# AltiumSTM32_shematic.net
KiCad netlist of a schematic drawn in Altium Designer
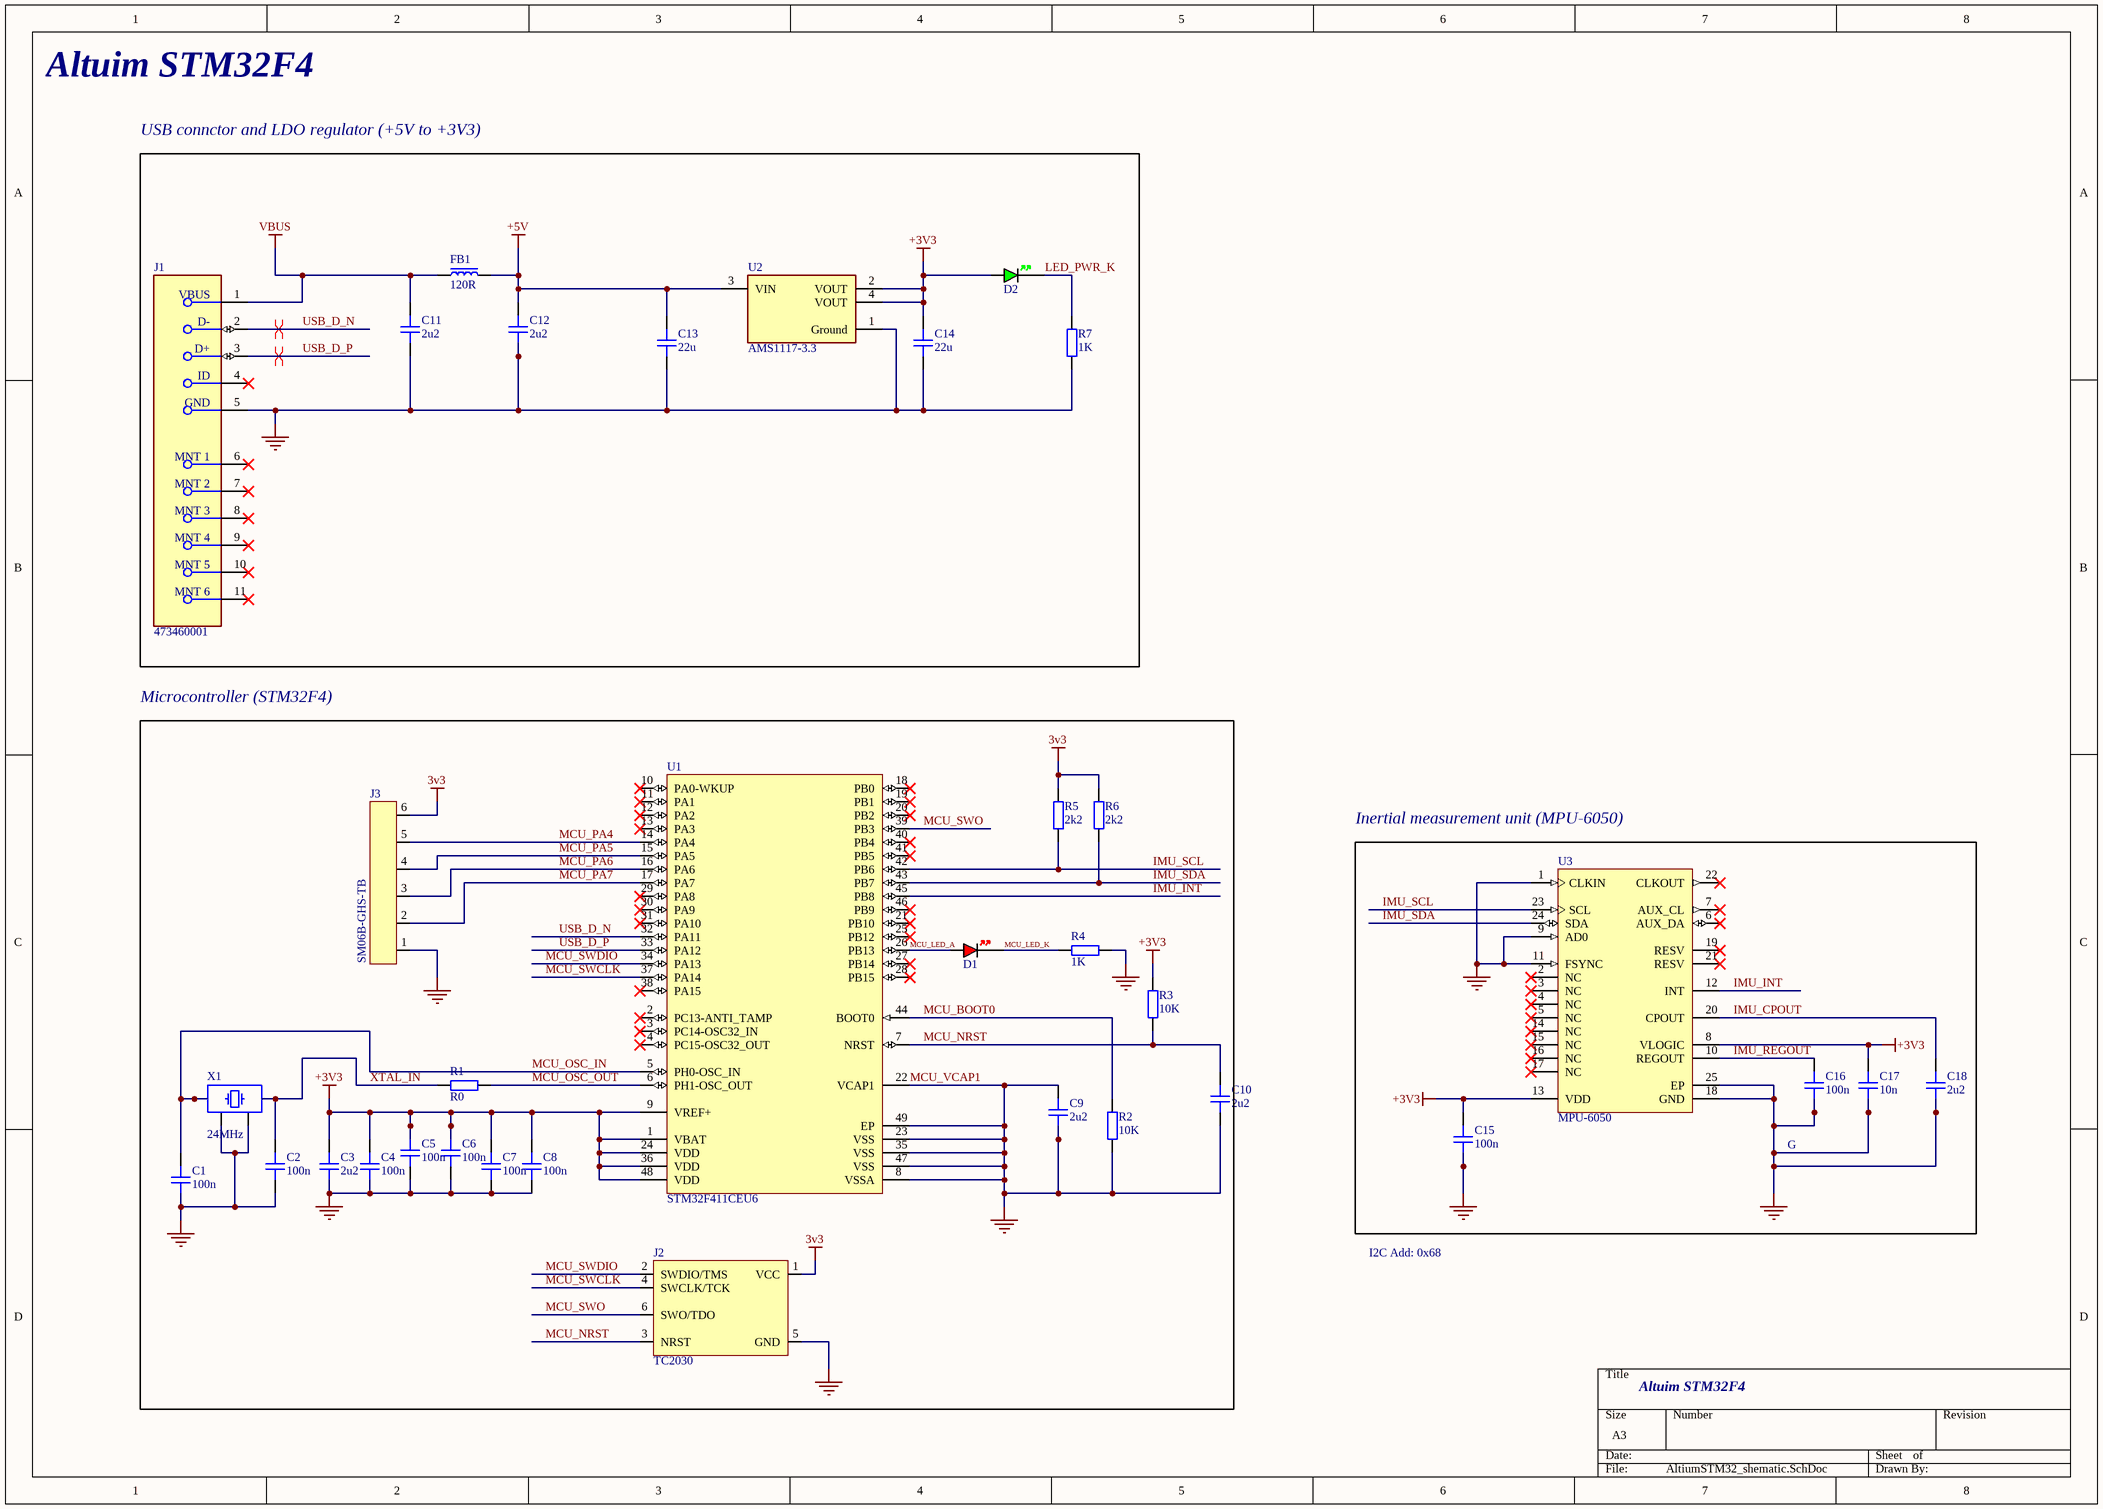
[diagram p0: AltiumSTM32_shematic.SchDoc]

(export (version "E")
  (design (tool "Eeschema 10.0.6"))
  (components
    (comp (ref "C1")
      (value "100n")
      (footprint "CAP_0402")
      (description "Capacitor SMD 0402")
      (libsource (lib "Schematic-Lib-PhilsLab") (part "CAP_0402"))
    )
    (comp (ref "C2")
      (value "100n")
      (footprint "CAP_0402")
      (description "Capacitor SMD 0402")
      (libsource (lib "Schematic-Lib-PhilsLab") (part "CAP_0402"))
    )
    (comp (ref "C3")
      (value "2u2")
      (footprint "CAP_0402")
      (description "Capacitor SMD 0402")
      (libsource (lib "Schematic-Lib-PhilsLab") (part "CAP_0402"))
    )
    (comp (ref "C4")
      (value "100n")
      (footprint "CAP_0402")
      (description "Capacitor SMD 0402")
      (libsource (lib "Schematic-Lib-PhilsLab") (part "CAP_0402"))
    )
    (comp (ref "C5")
      (value "100n")
      (footprint "CAP_0402")
      (description "Capacitor SMD 0402")
      (libsource (lib "Schematic-Lib-PhilsLab") (part "CAP_0402"))
    )
    (comp (ref "C6")
      (value "100n")
      (footprint "CAP_0402")
      (description "Capacitor SMD 0402")
      (libsource (lib "Schematic-Lib-PhilsLab") (part "CAP_0402"))
    )
    (comp (ref "C7")
      (value "100n")
      (footprint "CAP_0402")
      (description "Capacitor SMD 0402")
      (libsource (lib "Schematic-Lib-PhilsLab") (part "CAP_0402"))
    )
    (comp (ref "C8")
      (value "100n")
      (footprint "CAP_0402")
      (description "Capacitor SMD 0402")
      (libsource (lib "Schematic-Lib-PhilsLab") (part "CAP_0402"))
    )
    (comp (ref "C9")
      (value "2u2")
      (footprint "CAP_0402")
      (description "Capacitor SMD 0402")
      (libsource (lib "Schematic-Lib-PhilsLab") (part "CAP_0402"))
    )
    (comp (ref "C10")
      (value "2u2")
      (footprint "CAP_0402")
      (description "Capacitor SMD 0402")
      (libsource (lib "Schematic-Lib-PhilsLab") (part "CAP_0402"))
    )
    (comp (ref "C11")
      (value "2u2")
      (footprint "CAP_0402")
      (description "Capacitor SMD 0402")
      (libsource (lib "Schematic-Lib-PhilsLab") (part "CAP_0402"))
    )
    (comp (ref "C12")
      (value "2u2")
      (footprint "CAP_0402")
      (description "Capacitor SMD 0402")
      (libsource (lib "Schematic-Lib-PhilsLab") (part "CAP_0402"))
    )
    (comp (ref "C13")
      (value "22u")
      (footprint "CAP_0805")
      (description "Capacitor SMD 0805")
      (libsource (lib "Schematic-Lib-PhilsLab") (part "CAP_0805"))
    )
    (comp (ref "C14")
      (value "22u")
      (footprint "CAP_0805")
      (description "Capacitor SMD 0805")
      (libsource (lib "Schematic-Lib-PhilsLab") (part "CAP_0805"))
    )
    (comp (ref "C15")
      (value "100n")
      (footprint "CAP_0402")
      (description "Capacitor SMD 0402")
      (libsource (lib "Schematic-Lib-PhilsLab") (part "CAP_0402"))
    )
    (comp (ref "C16")
      (value "100n")
      (footprint "CAP_0402")
      (description "Capacitor SMD 0402")
      (libsource (lib "Schematic-Lib-PhilsLab") (part "CAP_0402"))
    )
    (comp (ref "C17")
      (value "10n")
      (footprint "CAP_0402")
      (description "Capacitor SMD 0402")
      (libsource (lib "Schematic-Lib-PhilsLab") (part "CAP_0402"))
    )
    (comp (ref "C18")
      (value "2u2")
      (footprint "CAP_0402")
      (description "Capacitor SMD 0402")
      (libsource (lib "Schematic-Lib-PhilsLab") (part "CAP_0402"))
    )
    (comp (ref "D1")
      (value "RED")
      (footprint "LED_0402_RED")
      (description "LED 0402 RED SMD")
      (libsource (lib "Schematic-Lib-PhilsLab") (part "LED_0402_RED"))
    )
    (comp (ref "D2")
      (value "GREEN")
      (footprint "LED_0402_GREEN")
      (description "LED 0402 GREEN SMD")
      (libsource (lib "Schematic-Lib-PhilsLab") (part "LED_0402_GREEN"))
    )
    (comp (ref "FB1")
      (value "120R")
      (footprint "FB_0402")
      (description "Ferrite Bead SMD 0402")
      (libsource (lib "Schematic-Lib-PhilsLab") (part "FB_0402"))
    )
    (comp (ref "J1")
      (value "473460001")
      (footprint "FP-473460001-MFG")
      (description "CONN RCPT USB2.0 MICRO B SMD R/A")
      (fields
        (field (name "OCTOPART") "https://octopart.com/47346-0001-molex-7164928")
        (field (name "MANUFACTURER") "Molex")
      )
      (libsource (lib "Altium Content Vault") (part "53ae1f1d9b557310b43ca686e5bb76a"))
    )
    (comp (ref "J2")
      (value "TC2030")
      (footprint "TC2030-FP")
      (description "Tag-Connect No-Solder SWD Debug Connector DO NOT PLACE")
      (fields (field (name "MANUFACTURER") "Tag-Connect"))
      (libsource (lib "Schematic-Lib-PhilsLab") (part "TC2030"))
    )
    (comp (ref "J3")
      (value "SM06B-GHS-TB")
      (footprint "SM06B-GHS-TB")
      (description "Header Connector 6 Position 1.25MM Pitch SMD Horizontal JST GH")
      (fields (field (name "MANUFACTURER") "JST"))
      (libsource (lib "Schematic-Lib-PhilsLab") (part "SM06B-GHS-TB"))
    )
    (comp (ref "R1")
      (value "R0")
      (footprint "RES_0402")
      (description "Resistor SMD 0402")
      (libsource (lib "Schematic-Lib-PhilsLab") (part "RES_0402"))
    )
    (comp (ref "R2")
      (value "10K")
      (footprint "RES_0402")
      (description "Resistor SMD 0402")
      (libsource (lib "Schematic-Lib-PhilsLab") (part "RES_0402"))
    )
    (comp (ref "R3")
      (value "10K")
      (footprint "RES_0402")
      (description "Resistor SMD 0402")
      (libsource (lib "Schematic-Lib-PhilsLab") (part "RES_0402"))
    )
    (comp (ref "R4")
      (value "1K")
      (footprint "RES_0402")
      (description "Resistor SMD 0402")
      (libsource (lib "Schematic-Lib-PhilsLab") (part "RES_0402"))
    )
    (comp (ref "R5")
      (value "2k2")
      (footprint "RES_0402")
      (description "Resistor SMD 0402")
      (libsource (lib "Schematic-Lib-PhilsLab") (part "RES_0402"))
    )
    (comp (ref "R6")
      (value "2k2")
      (footprint "RES_0402")
      (description "Resistor SMD 0402")
      (libsource (lib "Schematic-Lib-PhilsLab") (part "RES_0402"))
    )
    (comp (ref "R7")
      (value "1K")
      (footprint "RES_0402")
      (description "Resistor SMD 0402")
      (libsource (lib "Schematic-Lib-PhilsLab") (part "RES_0402"))
    )
    (comp (ref "U1")
      (value "STM32F411CEU6")
      (footprint "STM-UFQFPN48_L")
      (libsource (lib "Altium Content Vault") (part "MC-ARM-STM32F411-UFQFPN48"))
    )
    (comp (ref "U2")
      (value "AMS1117-3.3")
      (footprint "FP-AMS1117-IPC_C")
      (description "LDO Voltage Regulators 1A, 3.3V")
      (fields
        (field (name "OCTOPART") "https://octopart.com/ams1117-3.3-advanced+monolithic+systems-25899300")
        (field (name "MANUFACTURER") "Advanced Monolithic Systems")
      )
      (libsource (lib "Altium Content Vault") (part "8bdbb5f8e77002000e30dd2845d0354"))
    )
    (comp (ref "U3")
      (value "MPU-6050")
      (footprint "IS-QFN-24_V")
      (fields (field (name "MANUFACTURER") "InvenSense"))
      (libsource (lib "Altium Content Vault") (part "IS-MPU-6050-QFN-24"))
    )
    (comp (ref "X1")
      (value "24MHz")
      (footprint "XTAL_2016")
      (description "Crystal SMD 4-Pin 2.0x1.6mm")
      (libsource (lib "Schematic-Lib-PhilsLab") (part "XTAL_2016"))
    )
  )
  (nets
    (net (code "1") (name "+3V3") (class "Default")
      (node (ref "C14") (pin "2") (pinfunction "2_2") (pintype "passive"))
      (node (ref "C15") (pin "2") (pinfunction "2_2") (pintype "passive"))
      (node (ref "C17") (pin "2") (pinfunction "2_2") (pintype "passive"))
      (node (ref "C3") (pin "2") (pinfunction "2_2") (pintype "passive"))
      (node (ref "C4") (pin "2") (pinfunction "2_2") (pintype "passive"))
      (node (ref "C5") (pin "2") (pinfunction "2_2") (pintype "passive"))
      (node (ref "C6") (pin "2") (pinfunction "2_2") (pintype "passive"))
      (node (ref "C7") (pin "2") (pinfunction "2_2") (pintype "passive"))
      (node (ref "C8") (pin "2") (pinfunction "2_2") (pintype "passive"))
      (node (ref "D2") (pin "A") (pinfunction "A_A") (pintype "passive"))
      (node (ref "R3") (pin "2") (pinfunction "2_2") (pintype "passive"))
      (node (ref "U1") (pin "1") (pinfunction "VBAT_1") (pintype "power_in"))
      (node (ref "U1") (pin "24") (pinfunction "VDD_24") (pintype "power_in"))
      (node (ref "U1") (pin "36") (pinfunction "VDD_36") (pintype "power_in"))
      (node (ref "U1") (pin "48") (pinfunction "VDD_48") (pintype "power_in"))
      (node (ref "U1") (pin "9") (pinfunction "VREF+_9") (pintype "power_in"))
      (node (ref "U2") (pin "2") (pinfunction "VOUT_2") (pintype "passive"))
      (node (ref "U2") (pin "4") (pinfunction "VOUT_4") (pintype "passive"))
      (node (ref "U3") (pin "13") (pinfunction "VDD_13") (pintype "power_in"))
      (node (ref "U3") (pin "8") (pinfunction "VLOGIC_8") (pintype "power_in"))
    )
    (net (code "2") (name "+5V") (class "Default")
      (node (ref "C12") (pin "2") (pinfunction "2_2") (pintype "passive"))
      (node (ref "C13") (pin "2") (pinfunction "2_2") (pintype "passive"))
      (node (ref "FB1") (pin "2") (pinfunction "2_2") (pintype "passive"))
      (node (ref "U2") (pin "3") (pinfunction "VIN_3") (pintype "power_in"))
    )
    (net (code "3") (name "/IMU_CPOUT") (class "Default")
      (node (ref "C18") (pin "2") (pinfunction "2_2") (pintype "passive"))
      (node (ref "U3") (pin "20") (pinfunction "CPOUT_20") (pintype "passive"))
    )
    (net (code "4") (name "/IMU_INT") (class "Default")
      (node (ref "U1") (pin "45") (pinfunction "PB8_45") (pintype "bidirectional"))
      (node (ref "U3") (pin "12") (pinfunction "INT_12") (pintype "open_collector"))
    )
    (net (code "5") (name "/IMU_REGOUT") (class "Default")
      (node (ref "C16") (pin "2") (pinfunction "2_2") (pintype "passive"))
      (node (ref "U3") (pin "10") (pinfunction "REGOUT_10") (pintype "passive"))
    )
    (net (code "6") (name "/IMU_SCL") (class "Default")
      (node (ref "R5") (pin "1") (pinfunction "1_1") (pintype "passive"))
      (node (ref "U1") (pin "42") (pinfunction "PB6_42") (pintype "bidirectional"))
      (node (ref "U3") (pin "23") (pinfunction "SCL_23") (pintype "input"))
    )
    (net (code "7") (name "/IMU_SDA") (class "Default")
      (node (ref "R6") (pin "1") (pinfunction "1_1") (pintype "passive"))
      (node (ref "U1") (pin "43") (pinfunction "PB7_43") (pintype "bidirectional"))
      (node (ref "U3") (pin "24") (pinfunction "SDA_24") (pintype "bidirectional"))
    )
    (net (code "8") (name "/LED_PWR_K") (class "Default")
      (node (ref "D2") (pin "K") (pinfunction "K_K") (pintype "passive"))
      (node (ref "R7") (pin "2") (pinfunction "2_2") (pintype "passive"))
    )
    (net (code "9") (name "/MCU_BOOT0") (class "Default")
      (node (ref "R2") (pin "2") (pinfunction "2_2") (pintype "passive"))
      (node (ref "U1") (pin "44") (pinfunction "BOOT0_44") (pintype "input"))
    )
    (net (code "10") (name "/MCU_LED_A") (class "Default")
      (node (ref "D1") (pin "A") (pinfunction "A_A") (pintype "passive"))
      (node (ref "U1") (pin "26") (pinfunction "PB13_26") (pintype "bidirectional"))
    )
    (net (code "11") (name "/MCU_LED_K") (class "Default")
      (node (ref "D1") (pin "K") (pinfunction "K_K") (pintype "passive"))
      (node (ref "R4") (pin "2") (pinfunction "2_2") (pintype "passive"))
    )
    (net (code "12") (name "/MCU_NRST") (class "Default")
      (node (ref "C10") (pin "2") (pinfunction "2_2") (pintype "passive"))
      (node (ref "J2") (pin "3") (pinfunction "NRST_3") (pintype "passive"))
      (node (ref "R3") (pin "1") (pinfunction "1_1") (pintype "passive"))
      (node (ref "U1") (pin "7") (pinfunction "NRST_7") (pintype "bidirectional"))
    )
    (net (code "13") (name "/MCU_OSC_IN") (class "Default")
      (node (ref "C1") (pin "2") (pinfunction "2_2") (pintype "passive"))
      (node (ref "U1") (pin "5") (pinfunction "PH0-OSC_IN_5") (pintype "bidirectional"))
      (node (ref "X1") (pin "1") (pinfunction "1_1") (pintype "passive"))
    )
    (net (code "14") (name "/MCU_OSC_OUT") (class "Default")
      (node (ref "R1") (pin "2") (pinfunction "2_2") (pintype "passive"))
      (node (ref "U1") (pin "6") (pinfunction "PH1-OSC_OUT_6") (pintype "bidirectional"))
    )
    (net (code "15") (name "/MCU_PA4") (class "Default")
      (node (ref "J3") (pin "5") (pinfunction "5_5") (pintype "passive"))
      (node (ref "U1") (pin "14") (pinfunction "PA4_14") (pintype "bidirectional"))
    )
    (net (code "16") (name "/MCU_PA5") (class "Default")
      (node (ref "J3") (pin "4") (pinfunction "4_4") (pintype "passive"))
      (node (ref "U1") (pin "15") (pinfunction "PA5_15") (pintype "bidirectional"))
    )
    (net (code "17") (name "/MCU_PA6") (class "Default")
      (node (ref "J3") (pin "3") (pinfunction "3_3") (pintype "passive"))
      (node (ref "U1") (pin "16") (pinfunction "PA6_16") (pintype "bidirectional"))
    )
    (net (code "18") (name "/MCU_PA7") (class "Default")
      (node (ref "J3") (pin "2") (pinfunction "2_2") (pintype "passive"))
      (node (ref "U1") (pin "17") (pinfunction "PA7_17") (pintype "bidirectional"))
    )
    (net (code "19") (name "/MCU_SWCLK") (class "Default")
      (node (ref "J2") (pin "4") (pinfunction "SWCLK/TCK_4") (pintype "passive"))
      (node (ref "U1") (pin "37") (pinfunction "PA14_37") (pintype "bidirectional"))
    )
    (net (code "20") (name "/MCU_SWDIO") (class "Default")
      (node (ref "J2") (pin "2") (pinfunction "SWDIO/TMS_2") (pintype "passive"))
      (node (ref "U1") (pin "34") (pinfunction "PA13_34") (pintype "bidirectional"))
    )
    (net (code "21") (name "/MCU_SWO") (class "Default")
      (node (ref "J2") (pin "6") (pinfunction "SWO/TDO_6") (pintype "passive"))
      (node (ref "U1") (pin "39") (pinfunction "PB3_39") (pintype "bidirectional"))
    )
    (net (code "22") (name "/USB_D_N") (class "Default")
      (node (ref "J1") (pin "2") (pinfunction "D-_2") (pintype "bidirectional"))
      (node (ref "U1") (pin "32") (pinfunction "PA11_32") (pintype "bidirectional"))
    )
    (net (code "23") (name "/USB_D_P") (class "Default")
      (node (ref "J1") (pin "3") (pinfunction "D+_3") (pintype "bidirectional"))
      (node (ref "U1") (pin "33") (pinfunction "PA12_33") (pintype "bidirectional"))
    )
    (net (code "24") (name "/XTAL_IN") (class "Default")
      (node (ref "C2") (pin "2") (pinfunction "2_2") (pintype "passive"))
      (node (ref "R1") (pin "1") (pinfunction "1_1") (pintype "passive"))
      (node (ref "X1") (pin "3") (pinfunction "3_3") (pintype "passive"))
    )
    (net (code "25") (name "3v3") (class "Default")
      (node (ref "J2") (pin "1") (pinfunction "VCC_1") (pintype "passive"))
      (node (ref "J3") (pin "6") (pinfunction "6_6") (pintype "passive"))
      (node (ref "R5") (pin "2") (pinfunction "2_2") (pintype "passive"))
      (node (ref "R6") (pin "2") (pinfunction "2_2") (pintype "passive"))
    )
    (net (code "26") (name "G") (class "Default")
      (node (ref "C1") (pin "1") (pinfunction "1_1") (pintype "passive"))
      (node (ref "C2") (pin "1") (pinfunction "1_1") (pintype "passive"))
      (node (ref "C3") (pin "1") (pinfunction "1_1") (pintype "passive"))
      (node (ref "C4") (pin "1") (pinfunction "1_1") (pintype "passive"))
      (node (ref "C5") (pin "1") (pinfunction "1_1") (pintype "passive"))
      (node (ref "C6") (pin "1") (pinfunction "1_1") (pintype "passive"))
      (node (ref "C7") (pin "1") (pinfunction "1_1") (pintype "passive"))
      (node (ref "C8") (pin "1") (pinfunction "1_1") (pintype "passive"))
      (node (ref "X1") (pin "2") (pinfunction "2_2") (pintype "passive"))
      (node (ref "X1") (pin "4") (pinfunction "4_4") (pintype "passive"))
    )
    (net (code "27") (name "GND") (class "Default")
      (node (ref "C10") (pin "1") (pinfunction "1_1") (pintype "passive"))
      (node (ref "C11") (pin "1") (pinfunction "1_1") (pintype "passive"))
      (node (ref "C12") (pin "1") (pinfunction "1_1") (pintype "passive"))
      (node (ref "C13") (pin "1") (pinfunction "1_1") (pintype "passive"))
      (node (ref "C14") (pin "1") (pinfunction "1_1") (pintype "passive"))
      (node (ref "C15") (pin "1") (pinfunction "1_1") (pintype "passive"))
      (node (ref "C16") (pin "1") (pinfunction "1_1") (pintype "passive"))
      (node (ref "C17") (pin "1") (pinfunction "1_1") (pintype "passive"))
      (node (ref "C18") (pin "1") (pinfunction "1_1") (pintype "passive"))
      (node (ref "C9") (pin "1") (pinfunction "1_1") (pintype "passive"))
      (node (ref "C9") (pin "2") (pinfunction "2_2") (pintype "passive"))
      (node (ref "J1") (pin "5") (pinfunction "GND_5") (pintype "power_in"))
      (node (ref "J2") (pin "5") (pinfunction "GND_5") (pintype "passive"))
      (node (ref "J3") (pin "1") (pinfunction "1_1") (pintype "passive"))
      (node (ref "R2") (pin "1") (pinfunction "1_1") (pintype "passive"))
      (node (ref "R4") (pin "1") (pinfunction "1_1") (pintype "passive"))
      (node (ref "R7") (pin "1") (pinfunction "1_1") (pintype "passive"))
      (node (ref "U1") (pin "22") (pinfunction "VCAP1_22") (pintype "passive"))
      (node (ref "U1") (pin "23") (pinfunction "VSS_23") (pintype "power_in"))
      (node (ref "U1") (pin "35") (pinfunction "VSS_35") (pintype "power_in"))
      (node (ref "U1") (pin "47") (pinfunction "VSS_47") (pintype "power_in"))
      (node (ref "U1") (pin "49") (pinfunction "EP_49") (pintype "power_in"))
      (node (ref "U1") (pin "8") (pinfunction "VSSA_8") (pintype "power_in"))
      (node (ref "U2") (pin "1") (pinfunction "Ground_1") (pintype "power_in"))
      (node (ref "U3") (pin "1") (pinfunction "CLKIN_1") (pintype "input"))
      (node (ref "U3") (pin "11") (pinfunction "FSYNC_11") (pintype "input"))
      (node (ref "U3") (pin "18") (pinfunction "GND_18") (pintype "power_in"))
      (node (ref "U3") (pin "25") (pinfunction "EP_25") (pintype "power_in"))
      (node (ref "U3") (pin "9") (pinfunction "AD0_9") (pintype "input"))
    )
    (net (code "28") (name "VBUS") (class "Default")
      (node (ref "C11") (pin "2") (pinfunction "2_2") (pintype "passive"))
      (node (ref "FB1") (pin "1") (pinfunction "1_1") (pintype "passive"))
      (node (ref "J1") (pin "1") (pinfunction "VBUS_1") (pintype "power_in"))
    )
    (net (code "29") (name "unconnected-(J1-ID-Pad4)") (class "Default")
      (node (ref "J1") (pin "4") (pinfunction "ID_4") (pintype "passive+no_connect"))
    )
    (net (code "30") (name "unconnected-(J1-MNT_1-Pad6)") (class "Default")
      (node (ref "J1") (pin "6") (pinfunction "MNT_1_6") (pintype "passive+no_connect"))
    )
    (net (code "31") (name "unconnected-(J1-MNT_2-Pad7)") (class "Default")
      (node (ref "J1") (pin "7") (pinfunction "MNT_2_7") (pintype "passive+no_connect"))
    )
    (net (code "32") (name "unconnected-(J1-MNT_3-Pad8)") (class "Default")
      (node (ref "J1") (pin "8") (pinfunction "MNT_3_8") (pintype "passive+no_connect"))
    )
    (net (code "33") (name "unconnected-(J1-MNT_4-Pad9)") (class "Default")
      (node (ref "J1") (pin "9") (pinfunction "MNT_4_9") (pintype "passive+no_connect"))
    )
    (net (code "34") (name "unconnected-(J1-MNT_5-Pad10)") (class "Default")
      (node (ref "J1") (pin "10") (pinfunction "MNT_5_10") (pintype "passive+no_connect"))
    )
    (net (code "35") (name "unconnected-(J1-MNT_6-Pad11)") (class "Default")
      (node (ref "J1") (pin "11") (pinfunction "MNT_6_11") (pintype "passive+no_connect"))
    )
    (net (code "36") (name "unconnected-(U1-PA0-WKUP-Pad10)") (class "Default")
      (node (ref "U1") (pin "10") (pinfunction "PA0-WKUP_10") (pintype "bidirectional+no_connect"))
    )
    (net (code "37") (name "unconnected-(U1-PA1-Pad11)") (class "Default")
      (node (ref "U1") (pin "11") (pinfunction "PA1_11") (pintype "bidirectional+no_connect"))
    )
    (net (code "38") (name "unconnected-(U1-PA2-Pad12)") (class "Default")
      (node (ref "U1") (pin "12") (pinfunction "PA2_12") (pintype "bidirectional+no_connect"))
    )
    (net (code "39") (name "unconnected-(U1-PA3-Pad13)") (class "Default")
      (node (ref "U1") (pin "13") (pinfunction "PA3_13") (pintype "bidirectional+no_connect"))
    )
    (net (code "40") (name "unconnected-(U1-PA8-Pad29)") (class "Default")
      (node (ref "U1") (pin "29") (pinfunction "PA8_29") (pintype "bidirectional+no_connect"))
    )
    (net (code "41") (name "unconnected-(U1-PA9-Pad30)") (class "Default")
      (node (ref "U1") (pin "30") (pinfunction "PA9_30") (pintype "bidirectional+no_connect"))
    )
    (net (code "42") (name "unconnected-(U1-PA10-Pad31)") (class "Default")
      (node (ref "U1") (pin "31") (pinfunction "PA10_31") (pintype "bidirectional+no_connect"))
    )
    (net (code "43") (name "unconnected-(U1-PA15-Pad38)") (class "Default")
      (node (ref "U1") (pin "38") (pinfunction "PA15_38") (pintype "bidirectional+no_connect"))
    )
    (net (code "44") (name "unconnected-(U1-PB0-Pad18)") (class "Default")
      (node (ref "U1") (pin "18") (pinfunction "PB0_18") (pintype "bidirectional+no_connect"))
    )
    (net (code "45") (name "unconnected-(U1-PB1-Pad19)") (class "Default")
      (node (ref "U1") (pin "19") (pinfunction "PB1_19") (pintype "bidirectional+no_connect"))
    )
    (net (code "46") (name "unconnected-(U1-PB2-Pad20)") (class "Default")
      (node (ref "U1") (pin "20") (pinfunction "PB2_20") (pintype "bidirectional+no_connect"))
    )
    (net (code "47") (name "unconnected-(U1-PB4-Pad40)") (class "Default")
      (node (ref "U1") (pin "40") (pinfunction "PB4_40") (pintype "bidirectional+no_connect"))
    )
    (net (code "48") (name "unconnected-(U1-PB5-Pad41)") (class "Default")
      (node (ref "U1") (pin "41") (pinfunction "PB5_41") (pintype "bidirectional+no_connect"))
    )
    (net (code "49") (name "unconnected-(U1-PB9-Pad46)") (class "Default")
      (node (ref "U1") (pin "46") (pinfunction "PB9_46") (pintype "bidirectional+no_connect"))
    )
    (net (code "50") (name "unconnected-(U1-PB10-Pad21)") (class "Default")
      (node (ref "U1") (pin "21") (pinfunction "PB10_21") (pintype "bidirectional+no_connect"))
    )
    (net (code "51") (name "unconnected-(U1-PB12-Pad25)") (class "Default")
      (node (ref "U1") (pin "25") (pinfunction "PB12_25") (pintype "bidirectional+no_connect"))
    )
    (net (code "52") (name "unconnected-(U1-PB14-Pad27)") (class "Default")
      (node (ref "U1") (pin "27") (pinfunction "PB14_27") (pintype "bidirectional+no_connect"))
    )
    (net (code "53") (name "unconnected-(U1-PB15-Pad28)") (class "Default")
      (node (ref "U1") (pin "28") (pinfunction "PB15_28") (pintype "bidirectional+no_connect"))
    )
    (net (code "54") (name "unconnected-(U1-PC13-ANTI_TAMP-Pad2)") (class "Default")
      (node (ref "U1") (pin "2") (pinfunction "PC13-ANTI_TAMP_2") (pintype "bidirectional+no_connect"))
    )
    (net (code "55") (name "unconnected-(U1-PC14-OSC32_IN-Pad3)") (class "Default")
      (node (ref "U1") (pin "3") (pinfunction "PC14-OSC32_IN_3") (pintype "bidirectional+no_connect"))
    )
    (net (code "56") (name "unconnected-(U1-PC15-OSC32_OUT-Pad4)") (class "Default")
      (node (ref "U1") (pin "4") (pinfunction "PC15-OSC32_OUT_4") (pintype "bidirectional+no_connect"))
    )
    (net (code "57") (name "unconnected-(U3-AUX_CL-Pad7)") (class "Default")
      (node (ref "U3") (pin "7") (pinfunction "AUX_CL_7") (pintype "output+no_connect"))
    )
    (net (code "58") (name "unconnected-(U3-AUX_DA-Pad6)") (class "Default")
      (node (ref "U3") (pin "6") (pinfunction "AUX_DA_6") (pintype "bidirectional+no_connect"))
    )
    (net (code "59") (name "unconnected-(U3-CLKOUT-Pad22)") (class "Default")
      (node (ref "U3") (pin "22") (pinfunction "CLKOUT_22") (pintype "output+no_connect"))
    )
    (net (code "60") (name "unconnected-(U3-NC-Pad2)") (class "Default")
      (node (ref "U3") (pin "2") (pinfunction "NC_2") (pintype "passive+no_connect"))
    )
    (net (code "61") (name "unconnected-(U3-NC-Pad3)") (class "Default")
      (node (ref "U3") (pin "3") (pinfunction "NC_3") (pintype "passive+no_connect"))
    )
    (net (code "62") (name "unconnected-(U3-NC-Pad4)") (class "Default")
      (node (ref "U3") (pin "4") (pinfunction "NC_4") (pintype "passive+no_connect"))
    )
    (net (code "63") (name "unconnected-(U3-NC-Pad5)") (class "Default")
      (node (ref "U3") (pin "5") (pinfunction "NC_5") (pintype "passive+no_connect"))
    )
    (net (code "64") (name "unconnected-(U3-NC-Pad14)") (class "Default")
      (node (ref "U3") (pin "14") (pinfunction "NC_14") (pintype "passive+no_connect"))
    )
    (net (code "65") (name "unconnected-(U3-NC-Pad15)") (class "Default")
      (node (ref "U3") (pin "15") (pinfunction "NC_15") (pintype "passive+no_connect"))
    )
    (net (code "66") (name "unconnected-(U3-NC-Pad16)") (class "Default")
      (node (ref "U3") (pin "16") (pinfunction "NC_16") (pintype "passive+no_connect"))
    )
    (net (code "67") (name "unconnected-(U3-NC-Pad17)") (class "Default")
      (node (ref "U3") (pin "17") (pinfunction "NC_17") (pintype "passive+no_connect"))
    )
    (net (code "68") (name "unconnected-(U3-RESV-Pad19)") (class "Default")
      (node (ref "U3") (pin "19") (pinfunction "RESV_19") (pintype "passive+no_connect"))
    )
    (net (code "69") (name "unconnected-(U3-RESV-Pad21)") (class "Default")
      (node (ref "U3") (pin "21") (pinfunction "RESV_21") (pintype "passive+no_connect"))
    )
  )
)
